# MAX4239basedV2.net
KiCad netlist of a schematic drawn in EAGLE
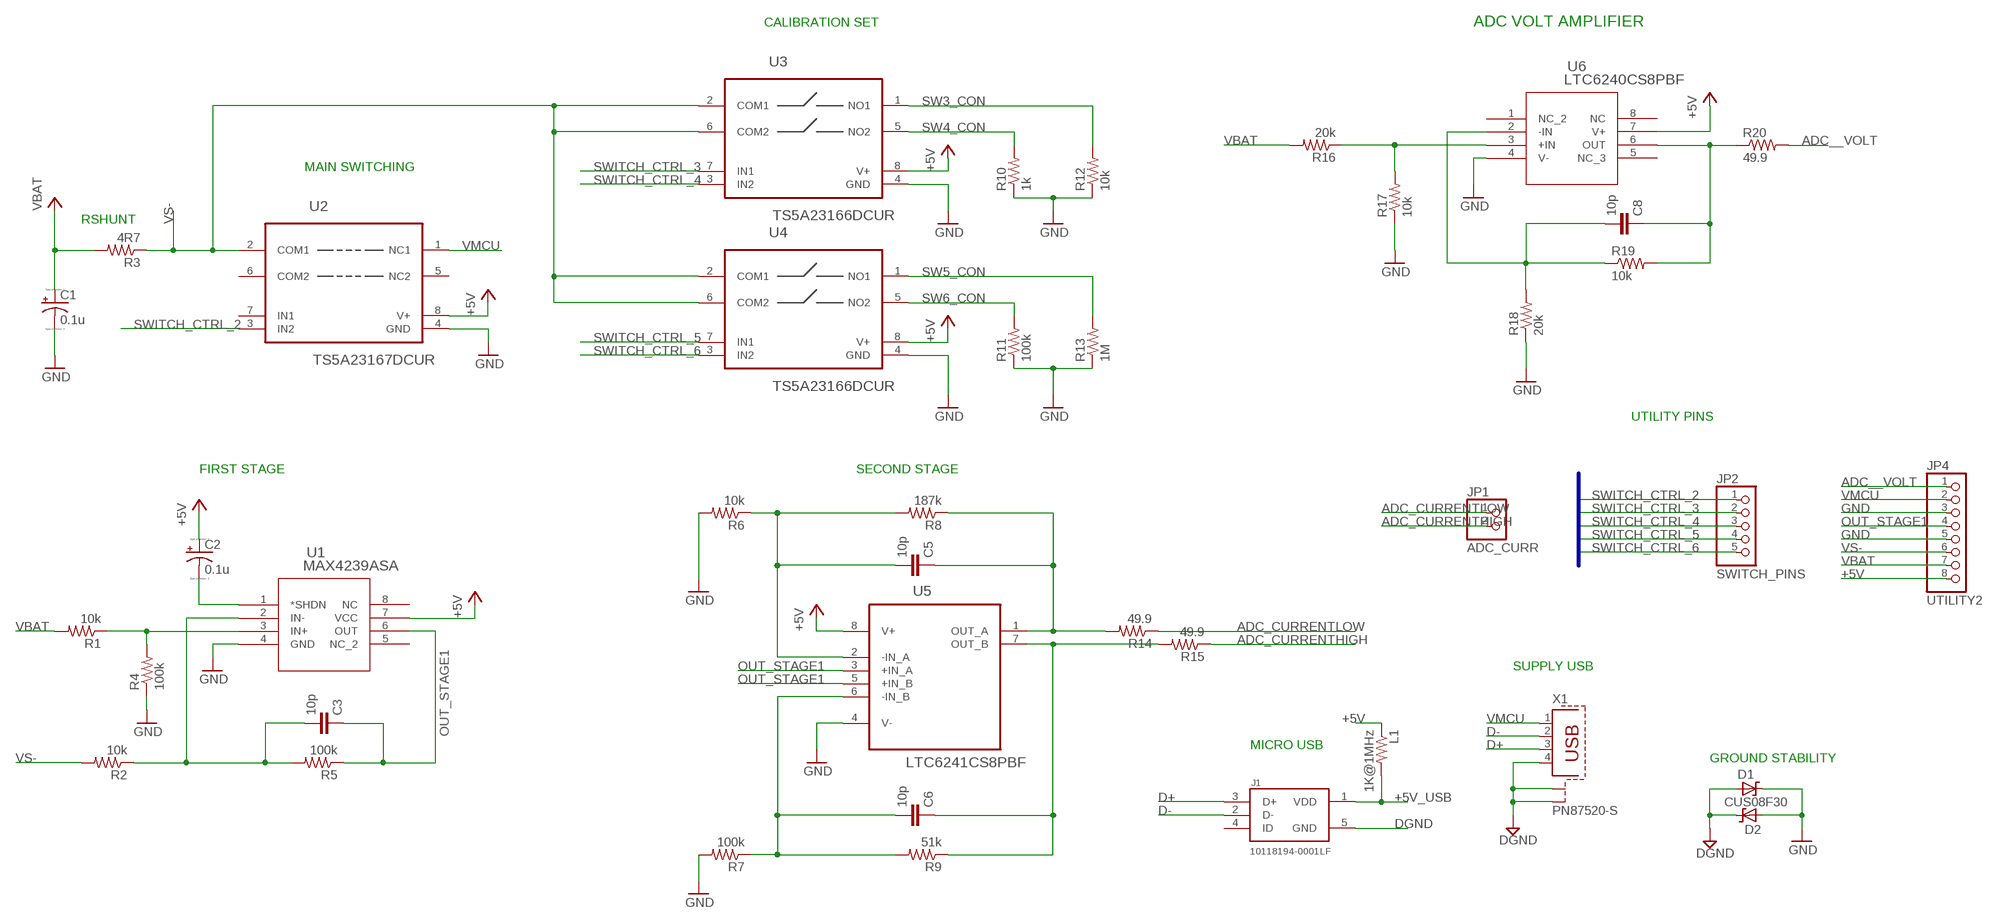
[diagram p0: schematic, sheet 1]

(export (version "E")
  (design (tool "Eeschema 10.0.6"))
  (components
    (comp (ref "C1")
      (value "0.1u")
      (footprint "eagle-import:PANASONIC_B")
      (libsource (lib "eagle-import") (part "CPOL-USB"))
    )
    (comp (ref "C2")
      (value "0.1u")
      (footprint "eagle-import:PANASONIC_B")
      (libsource (lib "eagle-import") (part "CPOL-USB"))
    )
    (comp (ref "C3")
      (value "10p")
      (footprint "eagle-import:C0805")
      (libsource (lib "eagle-import") (part "C-EUC0805"))
    )
    (comp (ref "C5")
      (value "10p")
      (footprint "eagle-import:C0805")
      (libsource (lib "eagle-import") (part "C-EUC0805"))
    )
    (comp (ref "C6")
      (value "10p")
      (footprint "eagle-import:C0805")
      (libsource (lib "eagle-import") (part "C-EUC0805"))
    )
    (comp (ref "C8")
      (value "10p")
      (footprint "eagle-import:C0805")
      (libsource (lib "eagle-import") (part "C-EUC0805"))
    )
    (comp (ref "D1")
      (value "CUS08F30")
      (footprint "eagle-import:SOD323")
      (fields (field (name "MF") "TOSHIBA"))
      (libsource (lib "eagle-import") (part "CUS08F30"))
    )
    (comp (ref "D2")
      (value "CUS08F30")
      (footprint "eagle-import:SOD323")
      (fields (field (name "MF") "TOSHIBA"))
      (libsource (lib "eagle-import") (part "CUS08F30"))
    )
    (comp (ref "J1")
      (value "10118194-0001LF")
      (footprint "eagle-import:FRAMATOME_10118194-0001LF")
      (fields (field (name "MF") "Amphenol"))
      (libsource (lib "eagle-import") (part "10118194-0001LF"))
    )
    (comp (ref "JP1")
      (value "ADC_CURR")
      (footprint "eagle-import:1X02")
      (libsource (lib "eagle-import") (part "PINHD-1X2"))
    )
    (comp (ref "JP2")
      (value "SWITCH_PINS")
      (footprint "eagle-import:1X05")
      (libsource (lib "eagle-import") (part "PINHD-1X5"))
    )
    (comp (ref "JP4")
      (value "UTILITY2")
      (footprint "eagle-import:1X08")
      (libsource (lib "eagle-import") (part "PINHD-1X8"))
    )
    (comp (ref "L1")
      (value "1K@1MHz")
      (footprint "eagle-import:R0805")
      (libsource (lib "eagle-import") (part "R-US_R0805"))
    )
    (comp (ref "R1")
      (value "10k")
      (footprint "eagle-import:R0805")
      (libsource (lib "eagle-import") (part "R-US_R0805"))
    )
    (comp (ref "R2")
      (value "10k")
      (footprint "eagle-import:R0805")
      (libsource (lib "eagle-import") (part "R-US_R0805"))
    )
    (comp (ref "R3")
      (value "4R7")
      (footprint "eagle-import:R0805")
      (libsource (lib "eagle-import") (part "R-US_R0805"))
    )
    (comp (ref "R4")
      (value "100k")
      (footprint "eagle-import:R0805")
      (libsource (lib "eagle-import") (part "R-US_R0805"))
    )
    (comp (ref "R5")
      (value "100k")
      (footprint "eagle-import:R0805")
      (libsource (lib "eagle-import") (part "R-US_R0805"))
    )
    (comp (ref "R6")
      (value "10k")
      (footprint "eagle-import:R0805")
      (libsource (lib "eagle-import") (part "R-US_R0805"))
    )
    (comp (ref "R7")
      (value "100k")
      (footprint "eagle-import:R0805")
      (libsource (lib "eagle-import") (part "R-US_R0805"))
    )
    (comp (ref "R8")
      (value "187k")
      (footprint "eagle-import:R0805")
      (libsource (lib "eagle-import") (part "R-US_R0805"))
    )
    (comp (ref "R9")
      (value "51k")
      (footprint "eagle-import:R0805")
      (libsource (lib "eagle-import") (part "R-US_R0805"))
    )
    (comp (ref "R10")
      (value "1k")
      (footprint "eagle-import:R0805")
      (libsource (lib "eagle-import") (part "R-US_R0805"))
    )
    (comp (ref "R11")
      (value "100k")
      (footprint "eagle-import:R0805")
      (libsource (lib "eagle-import") (part "R-US_R0805"))
    )
    (comp (ref "R12")
      (value "10k")
      (footprint "eagle-import:R0805")
      (libsource (lib "eagle-import") (part "R-US_R0805"))
    )
    (comp (ref "R13")
      (value "1M")
      (footprint "eagle-import:R0805")
      (libsource (lib "eagle-import") (part "R-US_R0805"))
    )
    (comp (ref "R14")
      (value "49.9")
      (footprint "eagle-import:R0805")
      (libsource (lib "eagle-import") (part "R-US_R0805"))
    )
    (comp (ref "R15")
      (value "49.9")
      (footprint "eagle-import:R0805")
      (libsource (lib "eagle-import") (part "R-US_R0805"))
    )
    (comp (ref "R16")
      (value "20k")
      (footprint "eagle-import:R0805")
      (libsource (lib "eagle-import") (part "R-US_R0805"))
    )
    (comp (ref "R17")
      (value "10k")
      (footprint "eagle-import:R0805")
      (libsource (lib "eagle-import") (part "R-US_R0805"))
    )
    (comp (ref "R18")
      (value "20k")
      (footprint "eagle-import:R0805")
      (libsource (lib "eagle-import") (part "R-US_R0805"))
    )
    (comp (ref "R19")
      (value "10k")
      (footprint "eagle-import:R0805")
      (libsource (lib "eagle-import") (part "R-US_R0805"))
    )
    (comp (ref "R20")
      (value "49.9")
      (footprint "eagle-import:R0805")
      (libsource (lib "eagle-import") (part "R-US_R0805"))
    )
    (comp (ref "U1")
      (value "MAX4239ASA")
      (footprint "eagle-import:21-0041B_8")
      (fields (field (name "MF") "Maxim Integrated") (field (name "MP") "MAX4239ASA+"))
      (libsource (lib "eagle-import") (part "MAX4239ASA"))
    )
    (comp (ref "U2")
      (value "TS5A23167DCUR")
      (footprint "eagle-import:SOP50P310X90-8N")
      (fields (field (name "MF") "Texas Instruments"))
      (libsource (lib "eagle-import") (part "TS5A23167DCUR"))
    )
    (comp (ref "U3")
      (value "TS5A23166DCUR")
      (footprint "eagle-import:SOP50P310X90-8N")
      (fields (field (name "MF") "Texas Instruments"))
      (libsource (lib "eagle-import") (part "TS5A23166DCUR"))
    )
    (comp (ref "U4")
      (value "TS5A23166DCUR")
      (footprint "eagle-import:SOP50P310X90-8N")
      (fields (field (name "MF") "Texas Instruments"))
      (libsource (lib "eagle-import") (part "TS5A23166DCUR"))
    )
    (comp (ref "U5")
      (value "LTC6241CS8PBF")
      (footprint "eagle-import:SOIC127P600X175-8N")
      (fields (field (name "MF") "Linear Technology") (field (name "MP") "LTC6241CS8#PBF"))
      (libsource (lib "eagle-import") (part "LTC6241CS8PBF"))
    )
    (comp (ref "U6")
      (value "LTC6240CS8PBF")
      (footprint "eagle-import:SO-8_S")
      (fields (field (name "MF") "Linear Technology") (field (name "MP") "LTC6240CS8#PBF"))
      (libsource (lib "eagle-import") (part "LTC6240CS8PBF"))
    )
    (comp (ref "X1")
      (value "PN87520-S")
      (footprint "eagle-import:PN87520-S")
      (libsource (lib "eagle-import") (part "PN87520-S"))
    )
  )
  (nets
    (net (code "1") (name "+5V") (class "Default")
      (node (ref "C2") (pin "+") (pinfunction "+_+") (pintype "passive"))
      (node (ref "JP4") (pin "8") (pinfunction "8_8") (pintype "passive"))
      (node (ref "L1") (pin "1") (pinfunction "1_1") (pintype "passive"))
      (node (ref "U1") (pin "7") (pinfunction "VCC_7") (pintype "power_in"))
      (node (ref "U2") (pin "8") (pinfunction "V+_8") (pintype "power_in"))
      (node (ref "U3") (pin "8") (pinfunction "V+_8") (pintype "power_in"))
      (node (ref "U4") (pin "8") (pinfunction "V+_8") (pintype "power_in"))
      (node (ref "U5") (pin "8") (pinfunction "V+_8") (pintype "power_in"))
      (node (ref "U6") (pin "7") (pinfunction "V+_7") (pintype "power_in"))
    )
    (net (code "2") (name "/+5V_USB") (class "Default")
      (node (ref "J1") (pin "1") (pinfunction "VDD_1") (pintype "power_in"))
      (node (ref "L1") (pin "2") (pinfunction "2_2") (pintype "passive"))
    )
    (net (code "3") (name "/ADC_CURRENTHIGH") (class "Default")
      (node (ref "JP1") (pin "2") (pinfunction "2_2") (pintype "passive"))
      (node (ref "R15") (pin "1") (pinfunction "1_1") (pintype "passive"))
    )
    (net (code "4") (name "/ADC_CURRENTLOW") (class "Default")
      (node (ref "JP1") (pin "1") (pinfunction "1_1") (pintype "passive"))
      (node (ref "R14") (pin "1") (pinfunction "1_1") (pintype "passive"))
    )
    (net (code "5") (name "/ADC__VOLT") (class "Default")
      (node (ref "JP4") (pin "1") (pinfunction "1_1") (pintype "passive"))
      (node (ref "R20") (pin "2") (pinfunction "2_2") (pintype "passive"))
    )
    (net (code "6") (name "/D+") (class "Default")
      (node (ref "J1") (pin "3") (pinfunction "D+_3") (pintype "bidirectional"))
      (node (ref "X1") (pin "3") (pinfunction "3_3") (pintype "passive"))
    )
    (net (code "7") (name "/D-") (class "Default")
      (node (ref "J1") (pin "2") (pinfunction "D-_2") (pintype "bidirectional"))
      (node (ref "X1") (pin "2") (pinfunction "2_2") (pintype "passive"))
    )
    (net (code "8") (name "/OUT_STAGE1") (class "Default")
      (node (ref "C3") (pin "1") (pinfunction "1_1") (pintype "passive"))
      (node (ref "JP4") (pin "4") (pinfunction "4_4") (pintype "passive"))
      (node (ref "R5") (pin "1") (pinfunction "1_1") (pintype "passive"))
      (node (ref "U1") (pin "6") (pinfunction "OUT_6") (pintype "output"))
      (node (ref "U5") (pin "3") (pinfunction "+IN_A_3") (pintype "input"))
      (node (ref "U5") (pin "5") (pinfunction "+IN_B_5") (pintype "input"))
    )
    (net (code "9") (name "/SW3_CON") (class "Default")
      (node (ref "R12") (pin "2") (pinfunction "2_2") (pintype "passive"))
      (node (ref "U3") (pin "1") (pinfunction "NO1_1") (pintype "bidirectional"))
    )
    (net (code "10") (name "/SW4_CON") (class "Default")
      (node (ref "R10") (pin "2") (pinfunction "2_2") (pintype "passive"))
      (node (ref "U3") (pin "5") (pinfunction "NO2_5") (pintype "bidirectional"))
    )
    (net (code "11") (name "/SW5_CON") (class "Default")
      (node (ref "R13") (pin "2") (pinfunction "2_2") (pintype "passive"))
      (node (ref "U4") (pin "1") (pinfunction "NO1_1") (pintype "bidirectional"))
    )
    (net (code "12") (name "/SW6_CON") (class "Default")
      (node (ref "R11") (pin "2") (pinfunction "2_2") (pintype "passive"))
      (node (ref "U4") (pin "5") (pinfunction "NO2_5") (pintype "bidirectional"))
    )
    (net (code "13") (name "/SWITCH_CTRL_2") (class "Default")
      (node (ref "JP2") (pin "1") (pinfunction "1_1") (pintype "passive"))
      (node (ref "U2") (pin "3") (pinfunction "IN2_3") (pintype "input"))
    )
    (net (code "14") (name "/SWITCH_CTRL_3") (class "Default")
      (node (ref "JP2") (pin "2") (pinfunction "2_2") (pintype "passive"))
      (node (ref "U3") (pin "7") (pinfunction "IN1_7") (pintype "input"))
    )
    (net (code "15") (name "/SWITCH_CTRL_4") (class "Default")
      (node (ref "JP2") (pin "3") (pinfunction "3_3") (pintype "passive"))
      (node (ref "U3") (pin "3") (pinfunction "IN2_3") (pintype "input"))
    )
    (net (code "16") (name "/SWITCH_CTRL_5") (class "Default")
      (node (ref "JP2") (pin "4") (pinfunction "4_4") (pintype "passive"))
      (node (ref "U4") (pin "7") (pinfunction "IN1_7") (pintype "input"))
    )
    (net (code "17") (name "/SWITCH_CTRL_6") (class "Default")
      (node (ref "JP2") (pin "5") (pinfunction "5_5") (pintype "passive"))
      (node (ref "U4") (pin "3") (pinfunction "IN2_3") (pintype "input"))
    )
    (net (code "18") (name "/VMCU") (class "Default")
      (node (ref "JP4") (pin "2") (pinfunction "2_2") (pintype "passive"))
      (node (ref "U2") (pin "1") (pinfunction "NC1_1") (pintype "bidirectional"))
      (node (ref "X1") (pin "1") (pinfunction "1_1") (pintype "passive"))
    )
    (net (code "19") (name "/VS-") (class "Default")
      (node (ref "JP4") (pin "6") (pinfunction "6_6") (pintype "passive"))
      (node (ref "R2") (pin "2") (pinfunction "2_2") (pintype "passive"))
      (node (ref "R3") (pin "1") (pinfunction "1_1") (pintype "passive"))
      (node (ref "U2") (pin "2") (pinfunction "COM1_2") (pintype "bidirectional"))
      (node (ref "U3") (pin "2") (pinfunction "COM1_2") (pintype "bidirectional"))
      (node (ref "U3") (pin "6") (pinfunction "COM2_6") (pintype "bidirectional"))
      (node (ref "U4") (pin "2") (pinfunction "COM1_2") (pintype "bidirectional"))
      (node (ref "U4") (pin "6") (pinfunction "COM2_6") (pintype "bidirectional"))
    )
    (net (code "20") (name "DGND") (class "Default")
      (node (ref "D1") (pin "A") (pinfunction "A_A") (pintype "passive"))
      (node (ref "D2") (pin "C") (pinfunction "C_C") (pintype "passive"))
      (node (ref "J1") (pin "5") (pinfunction "GND_5") (pintype "power_in"))
      (node (ref "X1") (pin "4") (pinfunction "4_4") (pintype "passive"))
      (node (ref "X1") (pin "S1") (pinfunction "S1_S1") (pintype "passive"))
      (node (ref "X1") (pin "S2") (pinfunction "S2_S2") (pintype "passive"))
    )
    (net (code "21") (name "GND") (class "Default")
      (node (ref "C1") (pin "-") (pinfunction "-_-") (pintype "passive"))
      (node (ref "D1") (pin "C") (pinfunction "C_C") (pintype "passive"))
      (node (ref "D2") (pin "A") (pinfunction "A_A") (pintype "passive"))
      (node (ref "JP4") (pin "3") (pinfunction "3_3") (pintype "passive"))
      (node (ref "JP4") (pin "5") (pinfunction "5_5") (pintype "passive"))
      (node (ref "R10") (pin "1") (pinfunction "1_1") (pintype "passive"))
      (node (ref "R11") (pin "1") (pinfunction "1_1") (pintype "passive"))
      (node (ref "R12") (pin "1") (pinfunction "1_1") (pintype "passive"))
      (node (ref "R13") (pin "1") (pinfunction "1_1") (pintype "passive"))
      (node (ref "R17") (pin "1") (pinfunction "1_1") (pintype "passive"))
      (node (ref "R18") (pin "1") (pinfunction "1_1") (pintype "passive"))
      (node (ref "R4") (pin "1") (pinfunction "1_1") (pintype "passive"))
      (node (ref "R6") (pin "2") (pinfunction "2_2") (pintype "passive"))
      (node (ref "R7") (pin "2") (pinfunction "2_2") (pintype "passive"))
      (node (ref "U1") (pin "4") (pinfunction "GND_4") (pintype "power_in"))
      (node (ref "U2") (pin "4") (pinfunction "GND_4") (pintype "passive"))
      (node (ref "U3") (pin "4") (pinfunction "GND_4") (pintype "passive"))
      (node (ref "U4") (pin "4") (pinfunction "GND_4") (pintype "passive"))
      (node (ref "U5") (pin "4") (pinfunction "V-_4") (pintype "power_in"))
      (node (ref "U6") (pin "4") (pinfunction "V-_4") (pintype "power_in"))
    )
    (net (code "22") (name "Net-(U1-*SHDN)") (class "Default")
      (node (ref "C2") (pin "-") (pinfunction "-_-") (pintype "passive"))
      (node (ref "U1") (pin "1") (pinfunction "*SHDN_1") (pintype "passive"))
    )
    (net (code "23") (name "Net-(U1-IN+)") (class "Default")
      (node (ref "R1") (pin "1") (pinfunction "1_1") (pintype "passive"))
      (node (ref "R4") (pin "2") (pinfunction "2_2") (pintype "passive"))
      (node (ref "U1") (pin "3") (pinfunction "IN+_3") (pintype "input"))
    )
    (net (code "24") (name "Net-(U1-IN-)") (class "Default")
      (node (ref "C3") (pin "2") (pinfunction "2_2") (pintype "passive"))
      (node (ref "R2") (pin "1") (pinfunction "1_1") (pintype "passive"))
      (node (ref "R5") (pin "2") (pinfunction "2_2") (pintype "passive"))
      (node (ref "U1") (pin "2") (pinfunction "IN-_2") (pintype "input"))
    )
    (net (code "25") (name "Net-(U5--IN_A)") (class "Default")
      (node (ref "C5") (pin "2") (pinfunction "2_2") (pintype "passive"))
      (node (ref "R6") (pin "1") (pinfunction "1_1") (pintype "passive"))
      (node (ref "R8") (pin "2") (pinfunction "2_2") (pintype "passive"))
      (node (ref "U5") (pin "2") (pinfunction "-IN_A_2") (pintype "input"))
    )
    (net (code "26") (name "Net-(U5--IN_B)") (class "Default")
      (node (ref "C6") (pin "2") (pinfunction "2_2") (pintype "passive"))
      (node (ref "R7") (pin "1") (pinfunction "1_1") (pintype "passive"))
      (node (ref "R9") (pin "2") (pinfunction "2_2") (pintype "passive"))
      (node (ref "U5") (pin "6") (pinfunction "-IN_B_6") (pintype "input"))
    )
    (net (code "27") (name "Net-(U5-OUT_A)") (class "Default")
      (node (ref "C5") (pin "1") (pinfunction "1_1") (pintype "passive"))
      (node (ref "R14") (pin "2") (pinfunction "2_2") (pintype "passive"))
      (node (ref "R8") (pin "1") (pinfunction "1_1") (pintype "passive"))
      (node (ref "U5") (pin "1") (pinfunction "OUT_A_1") (pintype "output"))
    )
    (net (code "28") (name "Net-(U5-OUT_B)") (class "Default")
      (node (ref "C6") (pin "1") (pinfunction "1_1") (pintype "passive"))
      (node (ref "R15") (pin "2") (pinfunction "2_2") (pintype "passive"))
      (node (ref "R9") (pin "1") (pinfunction "1_1") (pintype "passive"))
      (node (ref "U5") (pin "7") (pinfunction "OUT_B_7") (pintype "output"))
    )
    (net (code "29") (name "Net-(U6-+IN)") (class "Default")
      (node (ref "R16") (pin "1") (pinfunction "1_1") (pintype "passive"))
      (node (ref "R17") (pin "2") (pinfunction "2_2") (pintype "passive"))
      (node (ref "U6") (pin "3") (pinfunction "+IN_3") (pintype "input"))
    )
    (net (code "30") (name "Net-(U6--IN)") (class "Default")
      (node (ref "C8") (pin "2") (pinfunction "2_2") (pintype "passive"))
      (node (ref "R18") (pin "2") (pinfunction "2_2") (pintype "passive"))
      (node (ref "R19") (pin "1") (pinfunction "1_1") (pintype "passive"))
      (node (ref "U6") (pin "2") (pinfunction "-IN_2") (pintype "input"))
    )
    (net (code "31") (name "Net-(U6-OUT)") (class "Default")
      (node (ref "C8") (pin "1") (pinfunction "1_1") (pintype "passive"))
      (node (ref "R19") (pin "2") (pinfunction "2_2") (pintype "passive"))
      (node (ref "R20") (pin "1") (pinfunction "1_1") (pintype "passive"))
      (node (ref "U6") (pin "6") (pinfunction "OUT_6") (pintype "output"))
    )
    (net (code "32") (name "VBAT") (class "Default")
      (node (ref "C1") (pin "+") (pinfunction "+_+") (pintype "passive"))
      (node (ref "JP4") (pin "7") (pinfunction "7_7") (pintype "passive"))
      (node (ref "R1") (pin "2") (pinfunction "2_2") (pintype "passive"))
      (node (ref "R16") (pin "2") (pinfunction "2_2") (pintype "passive"))
      (node (ref "R3") (pin "2") (pinfunction "2_2") (pintype "passive"))
    )
    (net (code "33") (name "unconnected-(J1-ID-Pad4)") (class "Default")
      (node (ref "J1") (pin "4") (pinfunction "ID_4") (pintype "passive"))
    )
    (net (code "34") (name "unconnected-(U1-NC-Pad8)") (class "Default")
      (node (ref "U1") (pin "8") (pinfunction "NC_8") (pintype "passive"))
    )
    (net (code "35") (name "unconnected-(U1-NC_2-Pad5)") (class "Default")
      (node (ref "U1") (pin "5") (pinfunction "NC_2_5") (pintype "passive"))
    )
    (net (code "36") (name "unconnected-(U2-COM2-Pad6)") (class "Default")
      (node (ref "U2") (pin "6") (pinfunction "COM2_6") (pintype "bidirectional"))
    )
    (net (code "37") (name "unconnected-(U2-IN1-Pad7)") (class "Default")
      (node (ref "U2") (pin "7") (pinfunction "IN1_7") (pintype "input"))
    )
    (net (code "38") (name "unconnected-(U2-NC2-Pad5)") (class "Default")
      (node (ref "U2") (pin "5") (pinfunction "NC2_5") (pintype "bidirectional"))
    )
    (net (code "39") (name "unconnected-(U6-NC-Pad8)") (class "Default")
      (node (ref "U6") (pin "8") (pinfunction "NC_8") (pintype "no_connect"))
    )
    (net (code "40") (name "unconnected-(U6-NC_2-Pad1)") (class "Default")
      (node (ref "U6") (pin "1") (pinfunction "NC_2_1") (pintype "no_connect"))
    )
    (net (code "41") (name "unconnected-(U6-NC_3-Pad5)") (class "Default")
      (node (ref "U6") (pin "5") (pinfunction "NC_3_5") (pintype "no_connect"))
    )
  )
)
